# virtual_ground_4.net
KiCad netlist of a schematic drawn in EAGLE
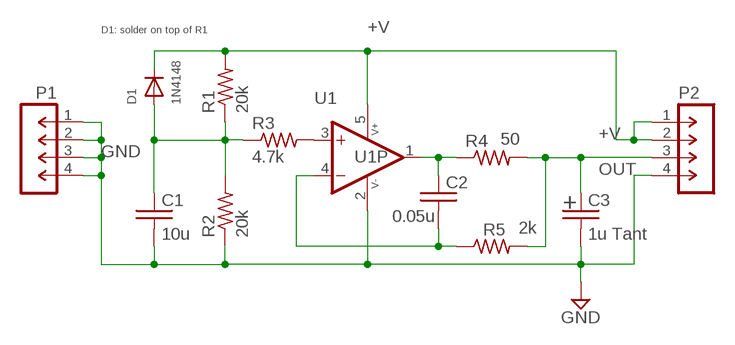
[diagram p0: schematic, sheet 1]

(export (version "E")
  (design (tool "Eeschema 10.0.6"))
  (components
    (comp (ref "C1")
      (value "10u")
      (footprint "eagle-import:C0805")
      (libsource (lib "eagle-import") (part "C-USC0805"))
    )
    (comp (ref "C2")
      (value "0.05u")
      (footprint "eagle-import:C0805")
      (libsource (lib "eagle-import") (part "C-USC0805"))
    )
    (comp (ref "C3")
      (value "1u Tant")
      (footprint "eagle-import:C0805")
      (libsource (lib "eagle-import") (part "C-USC0805"))
    )
    (comp (ref "D1")
      (value "1N4148")
      (footprint "eagle-import:SOD-323F")
      (libsource (lib "eagle-import") (part "DIODESOD-323F"))
    )
    (comp (ref "P1")
      (value "M-1X04-SIP-100-40")
      (footprint "eagle-import:SIP-100-04-40")
      (libsource (lib "eagle-import") (part "M-1X04-SIP-100-40"))
    )
    (comp (ref "P2")
      (value "M-1X04-")
      (footprint "eagle-import:SIP-100-04-40_DON")
      (libsource (lib "eagle-import") (part "M-1X04-"))
    )
    (comp (ref "R1")
      (value "20k")
      (footprint "eagle-import:R0805")
      (libsource (lib "eagle-import") (part "R-US_R0805"))
    )
    (comp (ref "R2")
      (value "20k")
      (footprint "eagle-import:R0805")
      (libsource (lib "eagle-import") (part "R-US_R0805"))
    )
    (comp (ref "R3")
      (value "4.7k")
      (footprint "eagle-import:R0805")
      (libsource (lib "eagle-import") (part "R-US_R0805"))
    )
    (comp (ref "R4")
      (value "50")
      (footprint "eagle-import:R0805")
      (libsource (lib "eagle-import") (part "R-US_R0805"))
    )
    (comp (ref "R5")
      (value "2k")
      (footprint "eagle-import:R0805")
      (libsource (lib "eagle-import") (part "R-US_R0805"))
    )
    (comp (ref "U1")
      (value "TLV9301IDBVR")
      (footprint "eagle-import:SOT23-5")
      (libsource (lib "eagle-import") (part "OPA846DBV"))
    )
  )
  (nets
    (net (code "1") (name "/+V") (class "Default")
      (node (ref "D1") (pin "C") (pinfunction "C_C") (pintype "passive"))
      (node (ref "P2") (pin "1") (pinfunction "1_1") (pintype "passive"))
      (node (ref "P2") (pin "2") (pinfunction "2_2") (pintype "passive"))
      (node (ref "R1") (pin "2") (pinfunction "2_2") (pintype "passive"))
      (node (ref "U1") (pin "5") (pinfunction "V+_5") (pintype "power_in"))
    )
    (net (code "2") (name "/OUT") (class "Default")
      (node (ref "C3") (pin "1") (pinfunction "1_1") (pintype "passive"))
      (node (ref "P2") (pin "3") (pinfunction "3_3") (pintype "passive"))
      (node (ref "R4") (pin "2") (pinfunction "2_2") (pintype "passive"))
      (node (ref "R5") (pin "2") (pinfunction "2_2") (pintype "passive"))
    )
    (net (code "3") (name "GND") (class "Default")
      (node (ref "C1") (pin "2") (pinfunction "2_2") (pintype "passive"))
      (node (ref "C3") (pin "2") (pinfunction "2_2") (pintype "passive"))
      (node (ref "P1") (pin "1") (pinfunction "1_1") (pintype "passive"))
      (node (ref "P1") (pin "2") (pinfunction "2_2") (pintype "passive"))
      (node (ref "P1") (pin "3") (pinfunction "3_3") (pintype "passive"))
      (node (ref "P1") (pin "4") (pinfunction "4_4") (pintype "passive"))
      (node (ref "P2") (pin "4") (pinfunction "4_4") (pintype "passive"))
      (node (ref "R2") (pin "1") (pinfunction "1_1") (pintype "passive"))
      (node (ref "U1") (pin "2") (pinfunction "V-_2") (pintype "power_in"))
    )
    (net (code "4") (name "Net-(C1-Pad1)") (class "Default")
      (node (ref "C1") (pin "1") (pinfunction "1_1") (pintype "passive"))
      (node (ref "D1") (pin "A") (pinfunction "A_A") (pintype "passive"))
      (node (ref "R1") (pin "1") (pinfunction "1_1") (pintype "passive"))
      (node (ref "R2") (pin "2") (pinfunction "2_2") (pintype "passive"))
      (node (ref "R3") (pin "1") (pinfunction "1_1") (pintype "passive"))
    )
    (net (code "5") (name "Net-(U1A-+IN)") (class "Default")
      (node (ref "R3") (pin "2") (pinfunction "2_2") (pintype "passive"))
      (node (ref "U1") (pin "3") (pinfunction "+IN_3") (pintype "input"))
    )
    (net (code "6") (name "Net-(U1A--IN)") (class "Default")
      (node (ref "C2") (pin "2") (pinfunction "2_2") (pintype "passive"))
      (node (ref "R5") (pin "1") (pinfunction "1_1") (pintype "passive"))
      (node (ref "U1") (pin "4") (pinfunction "-IN_4") (pintype "input"))
    )
    (net (code "7") (name "Net-(U1A-OUT)") (class "Default")
      (node (ref "C2") (pin "1") (pinfunction "1_1") (pintype "passive"))
      (node (ref "R4") (pin "1") (pinfunction "1_1") (pintype "passive"))
      (node (ref "U1") (pin "1") (pinfunction "OUT_1") (pintype "output"))
    )
  )
)
